# CircuitForPowermeter.net
KiCad netlist of a schematic drawn in Altium Designer
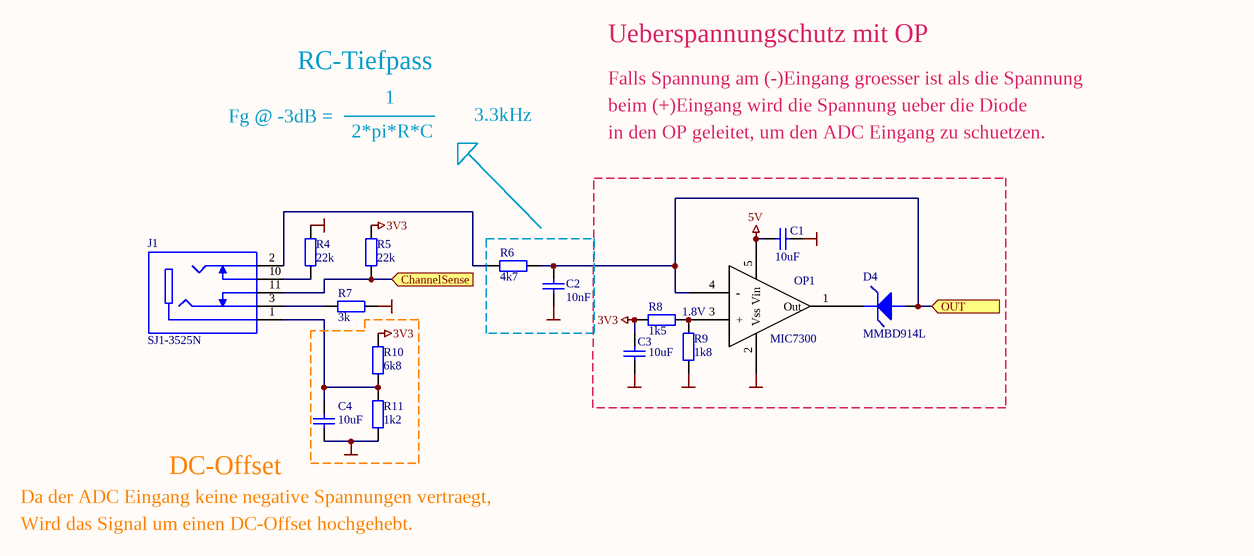
[diagram p0: CircuitForPowermeter.SchDoc]

(export (version "E")
  (design (tool "Eeschema 10.0.6"))
  (components
    (comp (ref "C1")
      (value "10uF")
      (footprint "1206_C")
      (description "Capacitor")
      (libsource (lib "passive") (part "C"))
    )
    (comp (ref "C2")
      (value "10nF")
      (footprint "0805")
      (description "Capacitor")
      (libsource (lib "passive") (part "C"))
    )
    (comp (ref "C3")
      (value "10uF")
      (footprint "1206_C")
      (description "Capacitor")
      (libsource (lib "passive") (part "C"))
    )
    (comp (ref "C4")
      (value "10uF")
      (footprint "1206_C")
      (description "Capacitor")
      (libsource (lib "passive") (part "C"))
    )
    (comp (ref "D4")
      (value "MMBD914L")
      (footprint "SOT-23")
      (description "High-Speed Switching  Diode")
      (libsource (lib "epc_cmd_default") (part "BZX84-B10"))
    )
    (comp (ref "J1")
      (value "SJ1-3525N")
      (footprint "CUI_SJ1-3525N")
      (description "3.5 mm, Stereo, Right Angle, Through Hole, Audio Jack Connector")
      (fields (field (name "MF") "CUI Devices"))
      (libsource (lib "AUXJack") (part "SJ1-3525N"))
    )
    (comp (ref "OP1")
      (value "MIC7300")
      (footprint "epc_cmd_default:SOT-23-5")
      (libsource (lib "OP") (part "Component_1"))
    )
    (comp (ref "R4")
      (value "22k")
      (footprint "0805_R")
      (description "Resistor")
      (libsource (lib "") (part "R_2"))
    )
    (comp (ref "R5")
      (value "22k")
      (footprint "0805_R")
      (description "Resistor")
      (libsource (lib "") (part "R_2"))
    )
    (comp (ref "R6")
      (value "4k7")
      (footprint "0805_R")
      (description "Resistor")
      (libsource (lib "passive") (part "R"))
    )
    (comp (ref "R7")
      (value "3k")
      (footprint "0805_R")
      (description "Resistor")
      (libsource (lib "") (part "R_3"))
    )
    (comp (ref "R8")
      (value "1k5")
      (footprint "0805_R")
      (description "Resistor")
      (libsource (lib "passive") (part "R"))
    )
    (comp (ref "R9")
      (value "1k8")
      (footprint "0805_R")
      (description "Resistor")
      (libsource (lib "") (part "R_1"))
    )
    (comp (ref "R10")
      (value "6k8")
      (footprint "0805_R")
      (description "Resistor")
      (libsource (lib "") (part "R_1"))
    )
    (comp (ref "R11")
      (value "1k2")
      (footprint "0805_R")
      (description "Resistor")
      (libsource (lib "") (part "R_1"))
    )
  )
  (nets
    (net (code "1") (name "/ChannelSense") (class "Default")
      (node (ref "J1") (pin "11") (pinfunction "11_11") (pintype "passive"))
      (node (ref "R5") (pin "2") (pinfunction "2_2") (pintype "passive"))
    )
    (net (code "2") (name "/OUT") (class "Default")
      (node (ref "C2") (pin "2") (pinfunction "2_2") (pintype "passive"))
      (node (ref "D4") (pin "1") (pinfunction "A_1") (pintype "passive"))
      (node (ref "OP1") (pin "4") (pinfunction "-_4") (pintype "passive"))
      (node (ref "R6") (pin "2") (pinfunction "2_2") (pintype "passive"))
    )
    (net (code "3") (name "3V3") (class "Default")
      (node (ref "C3") (pin "2") (pinfunction "2_2") (pintype "passive"))
      (node (ref "R10") (pin "2") (pinfunction "2_2") (pintype "passive"))
      (node (ref "R5") (pin "1") (pinfunction "1_1") (pintype "passive"))
      (node (ref "R8") (pin "1") (pinfunction "1_1") (pintype "passive"))
    )
    (net (code "4") (name "5V") (class "Default")
      (node (ref "C1") (pin "1") (pinfunction "1_1") (pintype "passive"))
      (node (ref "OP1") (pin "5") (pinfunction "Vin_5") (pintype "passive"))
    )
    (net (code "5") (name "<NO NET>") (class "Default")
      (node (ref "C1") (pin "2") (pinfunction "2_2") (pintype "passive"))
      (node (ref "C2") (pin "1") (pinfunction "1_1") (pintype "passive"))
      (node (ref "C3") (pin "1") (pinfunction "1_1") (pintype "passive"))
      (node (ref "C4") (pin "1") (pinfunction "1_1") (pintype "passive"))
      (node (ref "OP1") (pin "2") (pinfunction "Vss_2") (pintype "passive"))
      (node (ref "R11") (pin "1") (pinfunction "1_1") (pintype "passive"))
      (node (ref "R4") (pin "1") (pinfunction "1_1") (pintype "passive"))
      (node (ref "R7") (pin "1") (pinfunction "1_1") (pintype "passive"))
      (node (ref "R9") (pin "1") (pinfunction "1_1") (pintype "passive"))
    )
    (net (code "6") (name "Net-(C4-Pad2)") (class "Default")
      (node (ref "C4") (pin "2") (pinfunction "2_2") (pintype "passive"))
      (node (ref "J1") (pin "1") (pinfunction "1_1") (pintype "passive"))
      (node (ref "R10") (pin "1") (pinfunction "1_1") (pintype "passive"))
      (node (ref "R11") (pin "2") (pinfunction "2_2") (pintype "passive"))
    )
    (net (code "7") (name "Net-(D4-K)") (class "Default")
      (node (ref "D4") (pin "3") (pinfunction "K_3") (pintype "passive"))
      (node (ref "OP1") (pin "1") (pinfunction "Out_1") (pintype "passive"))
    )
    (net (code "8") (name "Net-(J1-Pad2)") (class "Default")
      (node (ref "J1") (pin "2") (pinfunction "2_2") (pintype "passive"))
      (node (ref "R6") (pin "1") (pinfunction "1_1") (pintype "passive"))
    )
    (net (code "9") (name "Net-(J1-Pad3)") (class "Default")
      (node (ref "J1") (pin "3") (pinfunction "3_3") (pintype "passive"))
      (node (ref "R7") (pin "2") (pinfunction "2_2") (pintype "passive"))
    )
    (net (code "10") (name "Net-(J1-Pad10)") (class "Default")
      (node (ref "J1") (pin "10") (pinfunction "10_10") (pintype "passive"))
      (node (ref "R4") (pin "2") (pinfunction "2_2") (pintype "passive"))
    )
    (net (code "11") (name "Net-(OP1-+)") (class "Default")
      (node (ref "OP1") (pin "3") (pinfunction "+_3") (pintype "passive"))
      (node (ref "R8") (pin "2") (pinfunction "2_2") (pintype "passive"))
      (node (ref "R9") (pin "2") (pinfunction "2_2") (pintype "passive"))
    )
    (net (code "12") (name "unconnected-(D4-NC-Pad2)") (class "Default")
      (node (ref "D4") (pin "2") (pinfunction "NC_2") (pintype "passive"))
    )
  )
)
